# power-dc_rev_1.net
KiCad netlist of a schematic drawn in EAGLE
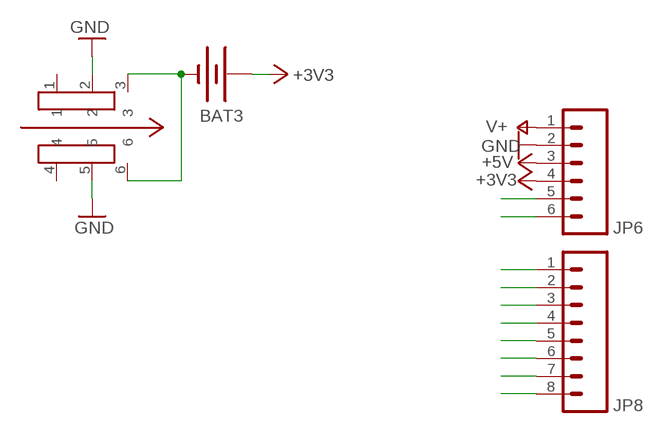
[diagram p0: schematic, sheet 1]

(export (version "E")
  (design (tool "Eeschema 10.0.6"))
  (components
    (comp (ref "BAT3")
      (value "BATTERY20PTH")
      (footprint "eagle-import:BATTCOM_20MM_PTH")
      (libsource (lib "eagle-import") (part "BATTERY20PTH"))
    )
    (comp (ref "JP6")
      (value "6")
      (footprint "eagle-import:1X06")
      (libsource (lib "eagle-import") (part "M06SIP"))
    )
    (comp (ref "JP8")
      (value "8")
      (footprint "eagle-import:1X08")
      (libsource (lib "eagle-import") (part "M081X08"))
    )
    (comp (ref "U$1")
      (value "SWITCH")
      (footprint "eagle-import:SWITCH")
      (libsource (lib "eagle-import") (part "SWITCH"))
    )
  )
  (nets
    (net (code "1") (name "+3V3") (class "Default")
      (node (ref "BAT3") (pin "1") (pinfunction "+_1") (pintype "power_in"))
      (node (ref "JP6") (pin "4") (pinfunction "4_4") (pintype "passive"))
    )
    (net (code "2") (name "+5V") (class "Default")
      (node (ref "JP6") (pin "3") (pinfunction "3_3") (pintype "passive"))
    )
    (net (code "3") (name "GND") (class "Default")
      (node (ref "JP6") (pin "2") (pinfunction "2_2") (pintype "passive"))
      (node (ref "U$1") (pin "2") (pinfunction "2_2") (pintype "bidirectional"))
      (node (ref "U$1") (pin "5") (pinfunction "5_5") (pintype "bidirectional"))
    )
    (net (code "4") (name "Net-(BAT3--)") (class "Default")
      (node (ref "BAT3") (pin "2") (pinfunction "-_2") (pintype "power_in"))
      (node (ref "U$1") (pin "3") (pinfunction "3_3") (pintype "bidirectional"))
      (node (ref "U$1") (pin "6") (pinfunction "6_6") (pintype "bidirectional"))
    )
    (net (code "5") (name "V+") (class "Default")
      (node (ref "JP6") (pin "1") (pinfunction "1_1") (pintype "passive"))
    )
    (net (code "6") (name "unconnected-(JP6-Pad5)") (class "Default")
      (node (ref "JP6") (pin "5") (pinfunction "5_5") (pintype "passive"))
    )
    (net (code "7") (name "unconnected-(JP6-Pad6)") (class "Default")
      (node (ref "JP6") (pin "6") (pinfunction "6_6") (pintype "passive"))
    )
    (net (code "8") (name "unconnected-(JP8-Pad1)") (class "Default")
      (node (ref "JP8") (pin "1") (pinfunction "1_1") (pintype "passive"))
    )
    (net (code "9") (name "unconnected-(JP8-Pad2)") (class "Default")
      (node (ref "JP8") (pin "2") (pinfunction "2_2") (pintype "passive"))
    )
    (net (code "10") (name "unconnected-(JP8-Pad3)") (class "Default")
      (node (ref "JP8") (pin "3") (pinfunction "3_3") (pintype "passive"))
    )
    (net (code "11") (name "unconnected-(JP8-Pad4)") (class "Default")
      (node (ref "JP8") (pin "4") (pinfunction "4_4") (pintype "passive"))
    )
    (net (code "12") (name "unconnected-(JP8-Pad5)") (class "Default")
      (node (ref "JP8") (pin "5") (pinfunction "5_5") (pintype "passive"))
    )
    (net (code "13") (name "unconnected-(JP8-Pad6)") (class "Default")
      (node (ref "JP8") (pin "6") (pinfunction "6_6") (pintype "passive"))
    )
    (net (code "14") (name "unconnected-(JP8-Pad7)") (class "Default")
      (node (ref "JP8") (pin "7") (pinfunction "7_7") (pintype "passive"))
    )
    (net (code "15") (name "unconnected-(JP8-Pad8)") (class "Default")
      (node (ref "JP8") (pin "8") (pinfunction "8_8") (pintype "passive"))
    )
    (net (code "16") (name "unconnected-(U$1-Pad1)") (class "Default")
      (node (ref "U$1") (pin "1") (pinfunction "1_1") (pintype "bidirectional"))
    )
    (net (code "17") (name "unconnected-(U$1-Pad4)") (class "Default")
      (node (ref "U$1") (pin "4") (pinfunction "4_4") (pintype "bidirectional"))
    )
  )
)
